# bottom.net
KiCad netlist of a schematic drawn in EAGLE
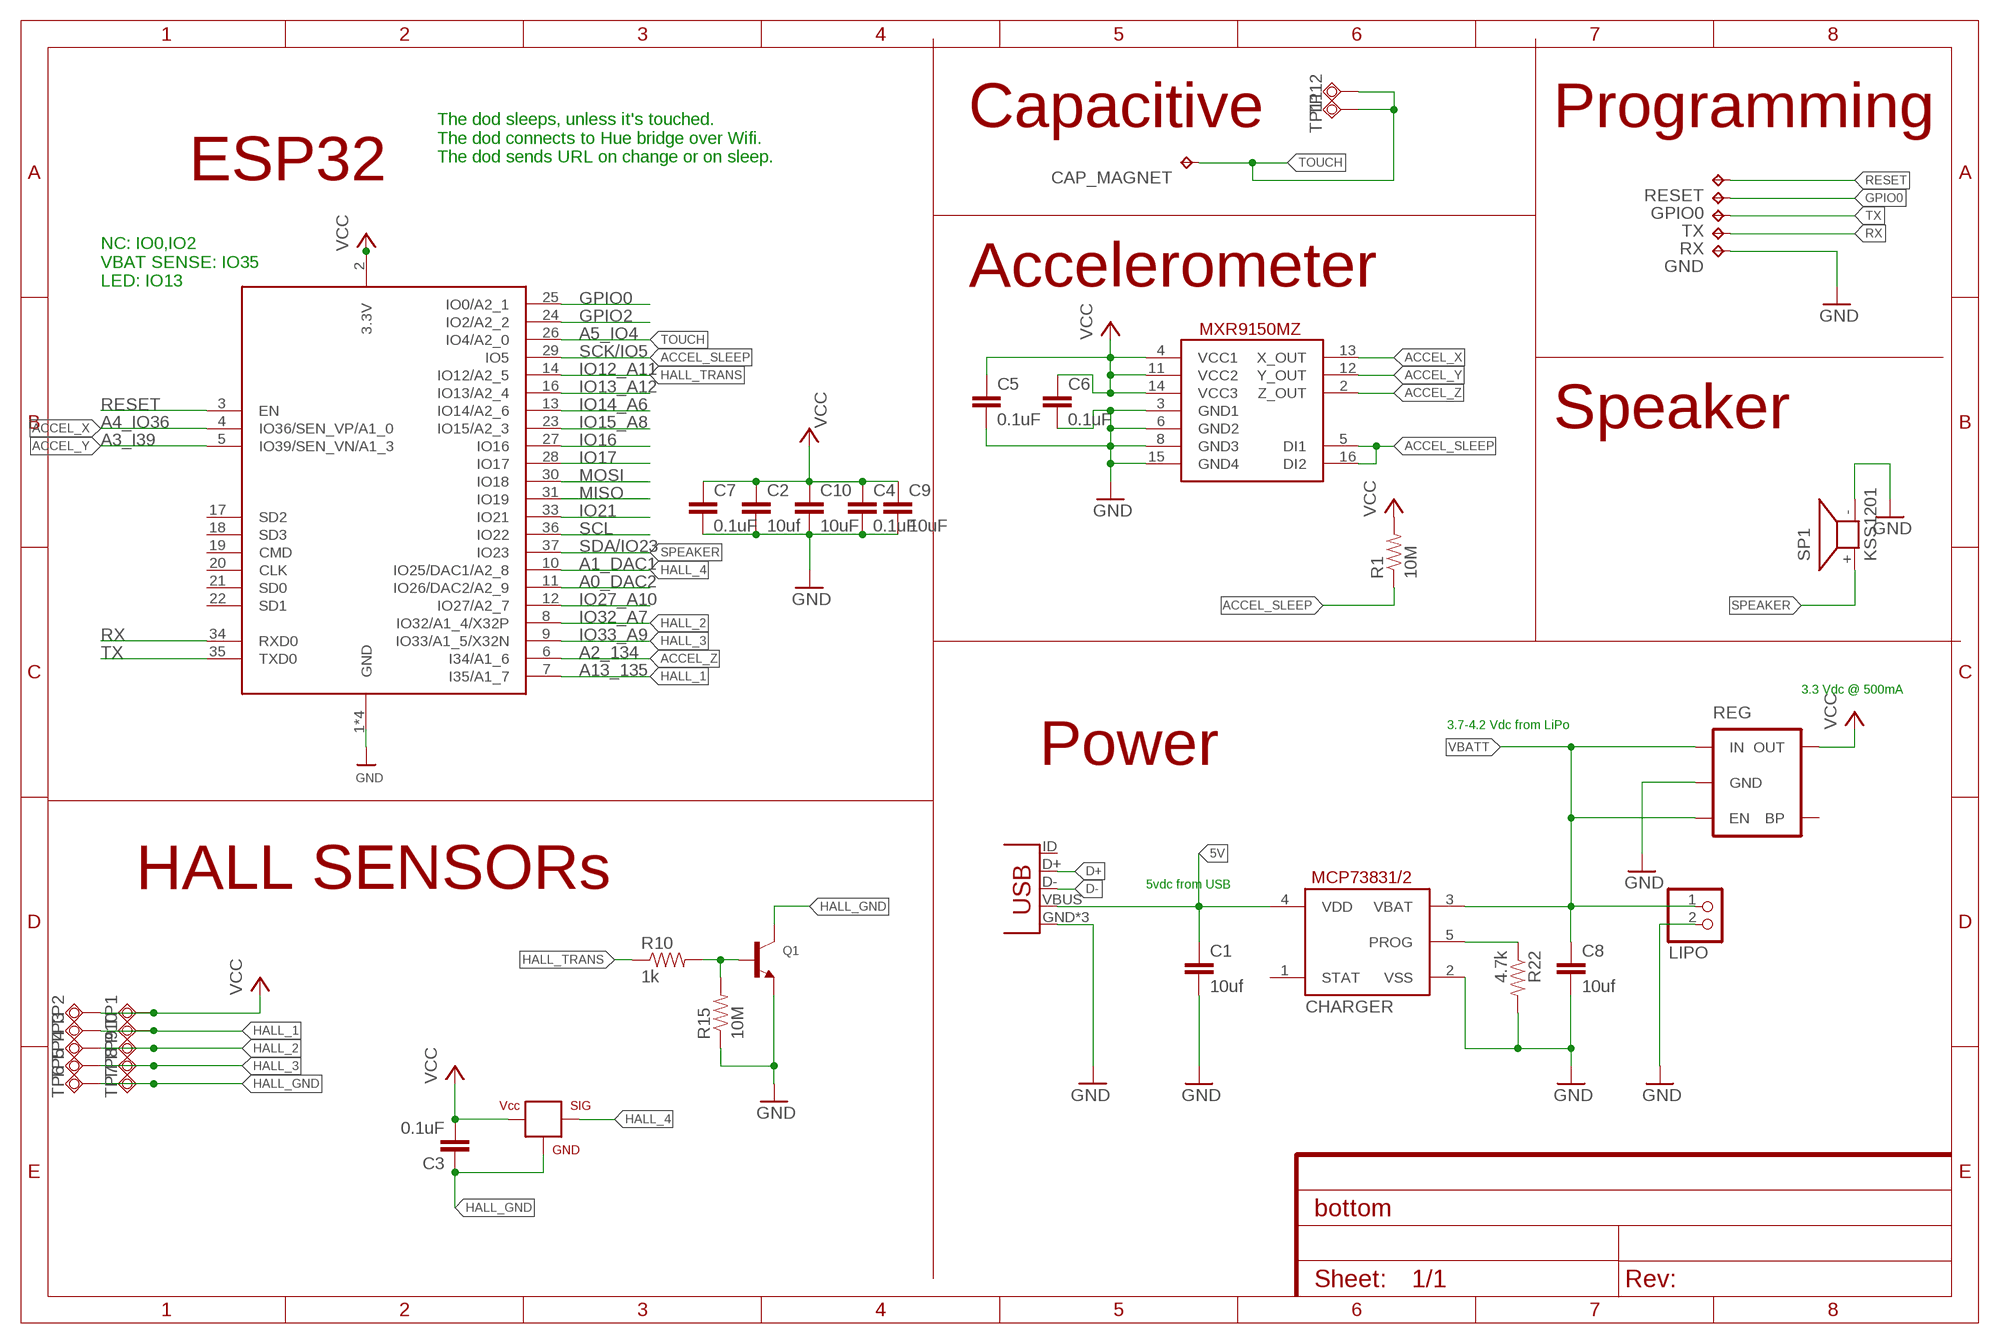
[diagram p0: schematic, sheet 1]

(export (version "E")
  (design (tool "Eeschema 10.0.6"))
  (components
    (comp (ref "C1")
      (value "10uf")
      (footprint "eagle-import:0603-CAP")
      (libsource (lib "eagle-import") (part "SparkFun-Capacitors_CAP0603-CAP"))
    )
    (comp (ref "C2")
      (value "10uf")
      (footprint "eagle-import:0402-CAP")
      (libsource (lib "eagle-import") (part "CAP0402-CAP"))
    )
    (comp (ref "C3")
      (value "0.1uF")
      (footprint "eagle-import:0603-CAP")
      (libsource (lib "eagle-import") (part "CAP0603-CAP"))
    )
    (comp (ref "C4")
      (value "0.1uF")
      (footprint "eagle-import:0402-CAP")
      (libsource (lib "eagle-import") (part "CAP0402-CAP"))
    )
    (comp (ref "C5")
      (value "0.1uF")
      (footprint "eagle-import:0402-CAP")
      (libsource (lib "eagle-import") (part "CAP0402-CAP"))
    )
    (comp (ref "C6")
      (value "0.1uF")
      (footprint "eagle-import:0402-CAP")
      (libsource (lib "eagle-import") (part "CAP0402-CAP"))
    )
    (comp (ref "C7")
      (value "0.1uF")
      (footprint "eagle-import:0402-CAP")
      (libsource (lib "eagle-import") (part "CAP0402-CAP"))
    )
    (comp (ref "C8")
      (value "10uf")
      (footprint "eagle-import:0603-CAP")
      (libsource (lib "eagle-import") (part "SparkFun-Capacitors_CAP0603-CAP"))
    )
    (comp (ref "C9")
      (value "10uF")
      (footprint "eagle-import:0402-CAP")
      (libsource (lib "eagle-import") (part "CAP0402-CAP"))
    )
    (comp (ref "C10")
      (value "10uF")
      (footprint "eagle-import:0402-CAP")
      (libsource (lib "eagle-import") (part "CAP0402-CAP"))
    )
    (comp (ref "CAP_MAGNET")
      (value "TPTP10R")
      (footprint "eagle-import:TP10R")
      (libsource (lib "eagle-import") (part "TPTP10R"))
    )
    (comp (ref "CHARGER")
      (value "MCP73831/OT")
      (footprint "eagle-import:SOT23-5L")
      (libsource (lib "eagle-import") (part "MCP73831/OT"))
    )
    (comp (ref "GND")
      (value "TPTP13SQ")
      (footprint "eagle-import:TP13SQ")
      (libsource (lib "eagle-import") (part "TPTP13SQ"))
    )
    (comp (ref "GPIO0")
      (value "TPTP13R")
      (footprint "eagle-import:TP13R")
      (libsource (lib "eagle-import") (part "TPTP13R"))
    )
    (comp (ref "HALL")
      (value "A1304")
      (footprint "eagle-import:SOT23-3")
      (libsource (lib "eagle-import") (part "HALLEFFECT-A1326"))
    )
    (comp (ref "JP1")
      (value "USB-MICROB")
      (footprint "eagle-import:USB-MICROB")
      (libsource (lib "eagle-import") (part "USB-MICROB"))
    )
    (comp (ref "LIPO")
      (value "JST_2PIN-THM")
      (footprint "eagle-import:JST-PH-2-THM")
      (libsource (lib "eagle-import") (part "JST_2PIN-THM"))
    )
    (comp (ref "Q1")
      (value "TRANSISTOR_NPN")
      (footprint "eagle-import:SOT-23-R")
      (libsource (lib "eagle-import") (part "TRANSISTOR_NPN"))
    )
    (comp (ref "R1")
      (value "10M")
      (footprint "eagle-import:0402-RES")
      (libsource (lib "eagle-import") (part "RESISTOR0402-RES"))
    )
    (comp (ref "R10")
      (value "1k")
      (footprint "eagle-import:0402-RES")
      (libsource (lib "eagle-import") (part "RESISTOR0402-RES"))
    )
    (comp (ref "R15")
      (value "10M")
      (footprint "eagle-import:0402-RES")
      (libsource (lib "eagle-import") (part "RESISTOR0402-RES"))
    )
    (comp (ref "R22")
      (value "4.7k")
      (footprint "eagle-import:0402-RES")
      (libsource (lib "eagle-import") (part "RESISTOR0402-RES"))
    )
    (comp (ref "REG")
      (value "MIC52053.3V")
      (footprint "eagle-import:SOT23-5")
      (libsource (lib "eagle-import") (part "MIC52053.3V"))
    )
    (comp (ref "RESET")
      (value "TPTP13R")
      (footprint "eagle-import:TP13R")
      (libsource (lib "eagle-import") (part "TPTP13R"))
    )
    (comp (ref "RX")
      (value "TPTP13R")
      (footprint "eagle-import:TP13R")
      (libsource (lib "eagle-import") (part "TPTP13R"))
    )
    (comp (ref "SP1")
      (value "KSS1201")
      (footprint "eagle-import:KSS1201")
      (libsource (lib "eagle-import") (part "KSS1201"))
    )
    (comp (ref "TP1")
      (value "TPSQTP10SQ")
      (footprint "eagle-import:TP10SQ")
      (libsource (lib "eagle-import") (part "TPSQTP10SQ"))
    )
    (comp (ref "TP2")
      (value "TPSQTP10SQ")
      (footprint "eagle-import:TP10SQ")
      (libsource (lib "eagle-import") (part "TPSQTP10SQ"))
    )
    (comp (ref "TP3")
      (value "TPSQTP10SQ")
      (footprint "eagle-import:TP10SQ")
      (libsource (lib "eagle-import") (part "TPSQTP10SQ"))
    )
    (comp (ref "TP4")
      (value "TPSQTP10SQ")
      (footprint "eagle-import:TP10SQ")
      (libsource (lib "eagle-import") (part "TPSQTP10SQ"))
    )
    (comp (ref "TP5")
      (value "TPSQTP10SQ")
      (footprint "eagle-import:TP10SQ")
      (libsource (lib "eagle-import") (part "TPSQTP10SQ"))
    )
    (comp (ref "TP6")
      (value "TPSQTP10SQ")
      (footprint "eagle-import:TP10SQ")
      (libsource (lib "eagle-import") (part "TPSQTP10SQ"))
    )
    (comp (ref "TP7")
      (value "TPSQTP10SQ")
      (footprint "eagle-import:TP10SQ")
      (libsource (lib "eagle-import") (part "TPSQTP10SQ"))
    )
    (comp (ref "TP8")
      (value "TPSQTP10SQ")
      (footprint "eagle-import:TP10SQ")
      (libsource (lib "eagle-import") (part "TPSQTP10SQ"))
    )
    (comp (ref "TP9")
      (value "TPSQTP10SQ")
      (footprint "eagle-import:TP10SQ")
      (libsource (lib "eagle-import") (part "TPSQTP10SQ"))
    )
    (comp (ref "TP10")
      (value "TPSQTP10SQ")
      (footprint "eagle-import:TP10SQ")
      (libsource (lib "eagle-import") (part "TPSQTP10SQ"))
    )
    (comp (ref "TP11")
      (value "TPSQTP10SQ")
      (footprint "eagle-import:TP10SQ")
      (libsource (lib "eagle-import") (part "TPSQTP10SQ"))
    )
    (comp (ref "TP12")
      (value "TPSQTP10SQ")
      (footprint "eagle-import:TP10SQ")
      (libsource (lib "eagle-import") (part "TPSQTP10SQ"))
    )
    (comp (ref "TX")
      (value "TPTP13R")
      (footprint "eagle-import:TP13R")
      (libsource (lib "eagle-import") (part "TPTP13R"))
    )
    (comp (ref "U$1")
      (value "ACCELEROMETER_MXR9150MZ")
      (footprint "eagle-import:MXR9150MZ")
      (libsource (lib "eagle-import") (part "ACCELEROMETER_MXR9150MZ"))
    )
    (comp (ref "X2")
      (value "ESP32_WROOM32_SKINNY")
      (footprint "eagle-import:WROOM32_SKINNY")
      (libsource (lib "eagle-import") (part "ESP32_WROOM32_SKINNY"))
    )
  )
  (nets
    (net (code "1") (name "/A0_DAC2") (class "Default")
      (node (ref "X2") (pin "11") (pinfunction "IO26/DAC2/A2_9_11") (pintype "bidirectional"))
    )
    (net (code "2") (name "/GPIO2") (class "Default")
      (node (ref "X2") (pin "24") (pinfunction "IO2/A2_2_24") (pintype "bidirectional"))
    )
    (net (code "3") (name "/IO16") (class "Default")
      (node (ref "X2") (pin "27") (pinfunction "IO16_27") (pintype "bidirectional"))
    )
    (net (code "4") (name "/IO17") (class "Default")
      (node (ref "X2") (pin "28") (pinfunction "IO17_28") (pintype "bidirectional"))
    )
    (net (code "5") (name "/IO21") (class "Default")
      (node (ref "X2") (pin "33") (pinfunction "IO21_33") (pintype "bidirectional"))
    )
    (net (code "6") (name "/MISO") (class "Default")
      (node (ref "X2") (pin "31") (pinfunction "IO19_31") (pintype "bidirectional"))
    )
    (net (code "7") (name "/MOSI") (class "Default")
      (node (ref "X2") (pin "30") (pinfunction "IO18_30") (pintype "bidirectional"))
    )
    (net (code "8") (name "/SCL") (class "Default")
      (node (ref "X2") (pin "36") (pinfunction "IO22_36") (pintype "bidirectional"))
    )
    (net (code "9") (name "5V") (class "Default")
      (node (ref "C1") (pin "1") (pinfunction "1_1") (pintype "passive"))
      (node (ref "CHARGER") (pin "4") (pinfunction "VDD_4") (pintype "power_in"))
      (node (ref "JP1") (pin "VBUS") (pinfunction "VBUS_VBUS") (pintype "bidirectional"))
    )
    (net (code "10") (name "ACCEL_SLEEP") (class "Default")
      (node (ref "R1") (pin "1") (pinfunction "1_1") (pintype "passive"))
      (node (ref "U$1") (pin "16") (pinfunction "DI2_16") (pintype "bidirectional"))
      (node (ref "U$1") (pin "5") (pinfunction "DI1_5") (pintype "bidirectional"))
      (node (ref "X2") (pin "29") (pinfunction "IO5_29") (pintype "bidirectional"))
    )
    (net (code "11") (name "ACCEL_X") (class "Default")
      (node (ref "U$1") (pin "13") (pinfunction "X_OUT_13") (pintype "bidirectional"))
      (node (ref "X2") (pin "4") (pinfunction "IO36/SEN_VP/A1_0_4") (pintype "passive"))
    )
    (net (code "12") (name "ACCEL_Y") (class "Default")
      (node (ref "U$1") (pin "12") (pinfunction "Y_OUT_12") (pintype "bidirectional"))
      (node (ref "X2") (pin "5") (pinfunction "IO39/SEN_VN/A1_3_5") (pintype "passive"))
    )
    (net (code "13") (name "ACCEL_Z") (class "Default")
      (node (ref "U$1") (pin "2") (pinfunction "Z_OUT_2") (pintype "bidirectional"))
      (node (ref "X2") (pin "6") (pinfunction "I34/A1_6_6") (pintype "bidirectional"))
    )
    (net (code "14") (name "D+") (class "Default")
      (node (ref "JP1") (pin "D+") (pinfunction "D+_D+") (pintype "bidirectional"))
    )
    (net (code "15") (name "D-") (class "Default")
      (node (ref "JP1") (pin "D-") (pinfunction "D-_D-") (pintype "bidirectional"))
    )
    (net (code "16") (name "GND") (class "Default")
      (node (ref "C1") (pin "2") (pinfunction "2_2") (pintype "passive"))
      (node (ref "C10") (pin "2") (pinfunction "2_2") (pintype "passive"))
      (node (ref "C2") (pin "2") (pinfunction "2_2") (pintype "passive"))
      (node (ref "C4") (pin "2") (pinfunction "2_2") (pintype "passive"))
      (node (ref "C5") (pin "2") (pinfunction "2_2") (pintype "passive"))
      (node (ref "C6") (pin "2") (pinfunction "2_2") (pintype "passive"))
      (node (ref "C7") (pin "2") (pinfunction "2_2") (pintype "passive"))
      (node (ref "C8") (pin "2") (pinfunction "2_2") (pintype "passive"))
      (node (ref "C9") (pin "2") (pinfunction "2_2") (pintype "passive"))
      (node (ref "CHARGER") (pin "2") (pinfunction "VSS_2") (pintype "power_in"))
      (node (ref "GND") (pin "TP") (pinfunction "TP_TP") (pintype "input"))
      (node (ref "JP1") (pin "GND") (pinfunction "GND_GND") (pintype "bidirectional"))
      (node (ref "JP1") (pin "MT1") (pinfunction "GND_MT1") (pintype "bidirectional"))
      (node (ref "JP1") (pin "MT2") (pinfunction "GND_MT2") (pintype "bidirectional"))
      (node (ref "LIPO") (pin "2") (pinfunction "1_2") (pintype "passive"))
      (node (ref "Q1") (pin "3-EMITTER") (pinfunction "E_3-EMITTER") (pintype "passive"))
      (node (ref "R15") (pin "1") (pinfunction "1_1") (pintype "passive"))
      (node (ref "R22") (pin "2") (pinfunction "2_2") (pintype "passive"))
      (node (ref "REG") (pin "2") (pinfunction "GND_2") (pintype "input"))
      (node (ref "SP1") (pin "-") (pinfunction "2_-") (pintype "passive"))
      (node (ref "U$1") (pin "15") (pinfunction "GND4_15") (pintype "bidirectional"))
      (node (ref "U$1") (pin "3") (pinfunction "GND1_3") (pintype "bidirectional"))
      (node (ref "U$1") (pin "6") (pinfunction "GND2_6") (pintype "bidirectional"))
      (node (ref "U$1") (pin "8") (pinfunction "GND3_8") (pintype "bidirectional"))
      (node (ref "X2") (pin "1") (pinfunction "GND_1") (pintype "passive"))
      (node (ref "X2") (pin "15") (pinfunction "GND_15") (pintype "passive"))
      (node (ref "X2") (pin "38") (pinfunction "GND_38") (pintype "passive"))
      (node (ref "X2") (pin "P$1") (pinfunction "GND_P$1") (pintype "passive"))
    )
    (net (code "17") (name "GPIO0") (class "Default")
      (node (ref "GPIO0") (pin "TP") (pinfunction "TP_TP") (pintype "input"))
      (node (ref "X2") (pin "25") (pinfunction "IO0/A2_1_25") (pintype "bidirectional"))
    )
    (net (code "18") (name "HALL_1") (class "Default")
      (node (ref "TP10") (pin "TP") (pinfunction "TP_TP") (pintype "input"))
      (node (ref "TP3") (pin "TP") (pinfunction "TP_TP") (pintype "input"))
      (node (ref "X2") (pin "7") (pinfunction "I35/A1_7_7") (pintype "bidirectional"))
    )
    (net (code "19") (name "HALL_2") (class "Default")
      (node (ref "TP4") (pin "TP") (pinfunction "TP_TP") (pintype "input"))
      (node (ref "TP9") (pin "TP") (pinfunction "TP_TP") (pintype "input"))
      (node (ref "X2") (pin "8") (pinfunction "IO32/A1_4/X32P_8") (pintype "bidirectional"))
    )
    (net (code "20") (name "HALL_3") (class "Default")
      (node (ref "TP5") (pin "TP") (pinfunction "TP_TP") (pintype "input"))
      (node (ref "TP8") (pin "TP") (pinfunction "TP_TP") (pintype "input"))
      (node (ref "X2") (pin "9") (pinfunction "IO33/A1_5/X32N_9") (pintype "bidirectional"))
    )
    (net (code "21") (name "HALL_4") (class "Default")
      (node (ref "HALL") (pin "2") (pinfunction "SIG_2") (pintype "bidirectional"))
      (node (ref "X2") (pin "10") (pinfunction "IO25/DAC1/A2_8_10") (pintype "bidirectional"))
    )
    (net (code "22") (name "HALL_GND") (class "Default")
      (node (ref "C3") (pin "1") (pinfunction "1_1") (pintype "passive"))
      (node (ref "HALL") (pin "3") (pinfunction "GND_3") (pintype "bidirectional"))
      (node (ref "Q1") (pin "2-COLLECTOR") (pinfunction "C_2-COLLECTOR") (pintype "passive"))
      (node (ref "TP6") (pin "TP") (pinfunction "TP_TP") (pintype "input"))
      (node (ref "TP7") (pin "TP") (pinfunction "TP_TP") (pintype "input"))
    )
    (net (code "23") (name "HALL_TRANS") (class "Default")
      (node (ref "R10") (pin "1") (pinfunction "1_1") (pintype "passive"))
      (node (ref "X2") (pin "14") (pinfunction "IO12/A2_5_14") (pintype "bidirectional"))
    )
    (net (code "24") (name "Net-(CHARGER-PROG)") (class "Default")
      (node (ref "CHARGER") (pin "5") (pinfunction "PROG_5") (pintype "input"))
      (node (ref "R22") (pin "1") (pinfunction "1_1") (pintype "passive"))
    )
    (net (code "25") (name "Net-(Q1-B)") (class "Default")
      (node (ref "Q1") (pin "1-BASE") (pinfunction "B_1-BASE") (pintype "passive"))
      (node (ref "R10") (pin "2") (pinfunction "2_2") (pintype "passive"))
      (node (ref "R15") (pin "2") (pinfunction "2_2") (pintype "passive"))
    )
    (net (code "26") (name "RESET") (class "Default")
      (node (ref "RESET") (pin "TP") (pinfunction "TP_TP") (pintype "input"))
      (node (ref "X2") (pin "3") (pinfunction "EN_3") (pintype "input"))
    )
    (net (code "27") (name "RX") (class "Default")
      (node (ref "RX") (pin "TP") (pinfunction "TP_TP") (pintype "input"))
      (node (ref "X2") (pin "34") (pinfunction "RXD0_34") (pintype "input"))
    )
    (net (code "28") (name "SPEAKER") (class "Default")
      (node (ref "SP1") (pin "+") (pinfunction "1_+") (pintype "passive"))
      (node (ref "X2") (pin "37") (pinfunction "IO23_37") (pintype "bidirectional"))
    )
    (net (code "29") (name "TOUCH") (class "Default")
      (node (ref "CAP_MAGNET") (pin "TP") (pinfunction "TP_TP") (pintype "input"))
      (node (ref "TP11") (pin "TP") (pinfunction "TP_TP") (pintype "input"))
      (node (ref "TP12") (pin "TP") (pinfunction "TP_TP") (pintype "input"))
      (node (ref "X2") (pin "26") (pinfunction "IO4/A2_0_26") (pintype "bidirectional"))
    )
    (net (code "30") (name "TX") (class "Default")
      (node (ref "TX") (pin "TP") (pinfunction "TP_TP") (pintype "input"))
      (node (ref "X2") (pin "35") (pinfunction "TXD0_35") (pintype "output"))
    )
    (net (code "31") (name "VBATT") (class "Default")
      (node (ref "C8") (pin "1") (pinfunction "1_1") (pintype "passive"))
      (node (ref "CHARGER") (pin "3") (pinfunction "VBAT_3") (pintype "bidirectional"))
      (node (ref "LIPO") (pin "1") (pinfunction "2_1") (pintype "passive"))
      (node (ref "REG") (pin "1") (pinfunction "IN_1") (pintype "input"))
      (node (ref "REG") (pin "3") (pinfunction "EN_3") (pintype "input"))
    )
    (net (code "32") (name "VCC") (class "Default")
      (node (ref "C10") (pin "1") (pinfunction "1_1") (pintype "passive"))
      (node (ref "C2") (pin "1") (pinfunction "1_1") (pintype "passive"))
      (node (ref "C3") (pin "2") (pinfunction "2_2") (pintype "passive"))
      (node (ref "C4") (pin "1") (pinfunction "1_1") (pintype "passive"))
      (node (ref "C5") (pin "1") (pinfunction "1_1") (pintype "passive"))
      (node (ref "C6") (pin "1") (pinfunction "1_1") (pintype "passive"))
      (node (ref "C7") (pin "1") (pinfunction "1_1") (pintype "passive"))
      (node (ref "C9") (pin "1") (pinfunction "1_1") (pintype "passive"))
      (node (ref "HALL") (pin "1") (pinfunction "VCC_1") (pintype "bidirectional"))
      (node (ref "R1") (pin "2") (pinfunction "2_2") (pintype "passive"))
      (node (ref "REG") (pin "5") (pinfunction "OUT_5") (pintype "passive"))
      (node (ref "TP1") (pin "TP") (pinfunction "TP_TP") (pintype "input"))
      (node (ref "TP2") (pin "TP") (pinfunction "TP_TP") (pintype "input"))
      (node (ref "U$1") (pin "11") (pinfunction "VCC2_11") (pintype "bidirectional"))
      (node (ref "U$1") (pin "14") (pinfunction "VCC3_14") (pintype "bidirectional"))
      (node (ref "U$1") (pin "4") (pinfunction "VCC1_4") (pintype "bidirectional"))
      (node (ref "X2") (pin "2") (pinfunction "3.3V_2") (pintype "passive"))
    )
    (net (code "33") (name "unconnected-(CHARGER-STAT-Pad1)") (class "Default")
      (node (ref "CHARGER") (pin "1") (pinfunction "STAT_1") (pintype "output"))
    )
    (net (code "34") (name "unconnected-(JP1-SHIELD-PadID)") (class "Default")
      (node (ref "JP1") (pin "ID") (pinfunction "SHIELD_ID") (pintype "bidirectional"))
    )
    (net (code "35") (name "unconnected-(REG-BP-Pad4)") (class "Default")
      (node (ref "REG") (pin "4") (pinfunction "BP_4") (pintype "input"))
    )
    (net (code "36") (name "unconnected-(X2-CLK-Pad20)") (class "Default")
      (node (ref "X2") (pin "20") (pinfunction "CLK_20") (pintype "bidirectional"))
    )
    (net (code "37") (name "unconnected-(X2-CMD-Pad19)") (class "Default")
      (node (ref "X2") (pin "19") (pinfunction "CMD_19") (pintype "bidirectional"))
    )
    (net (code "38") (name "unconnected-(X2-IO13{slash}A2_4-Pad16)") (class "Default")
      (node (ref "X2") (pin "16") (pinfunction "IO13/A2_4_16") (pintype "bidirectional"))
    )
    (net (code "39") (name "unconnected-(X2-IO14{slash}A2_6-Pad13)") (class "Default")
      (node (ref "X2") (pin "13") (pinfunction "IO14/A2_6_13") (pintype "bidirectional"))
    )
    (net (code "40") (name "unconnected-(X2-IO15{slash}A2_3-Pad23)") (class "Default")
      (node (ref "X2") (pin "23") (pinfunction "IO15/A2_3_23") (pintype "bidirectional"))
    )
    (net (code "41") (name "unconnected-(X2-IO27{slash}A2_7-Pad12)") (class "Default")
      (node (ref "X2") (pin "12") (pinfunction "IO27/A2_7_12") (pintype "bidirectional"))
    )
    (net (code "42") (name "unconnected-(X2-SD0-Pad21)") (class "Default")
      (node (ref "X2") (pin "21") (pinfunction "SD0_21") (pintype "bidirectional"))
    )
    (net (code "43") (name "unconnected-(X2-SD1-Pad22)") (class "Default")
      (node (ref "X2") (pin "22") (pinfunction "SD1_22") (pintype "bidirectional"))
    )
    (net (code "44") (name "unconnected-(X2-SD2-Pad17)") (class "Default")
      (node (ref "X2") (pin "17") (pinfunction "SD2_17") (pintype "bidirectional"))
    )
    (net (code "45") (name "unconnected-(X2-SD3-Pad18)") (class "Default")
      (node (ref "X2") (pin "18") (pinfunction "SD3_18") (pintype "bidirectional"))
    )
  )
)
